# schematic.net
KiCad netlist of a schematic drawn in EasyEDA
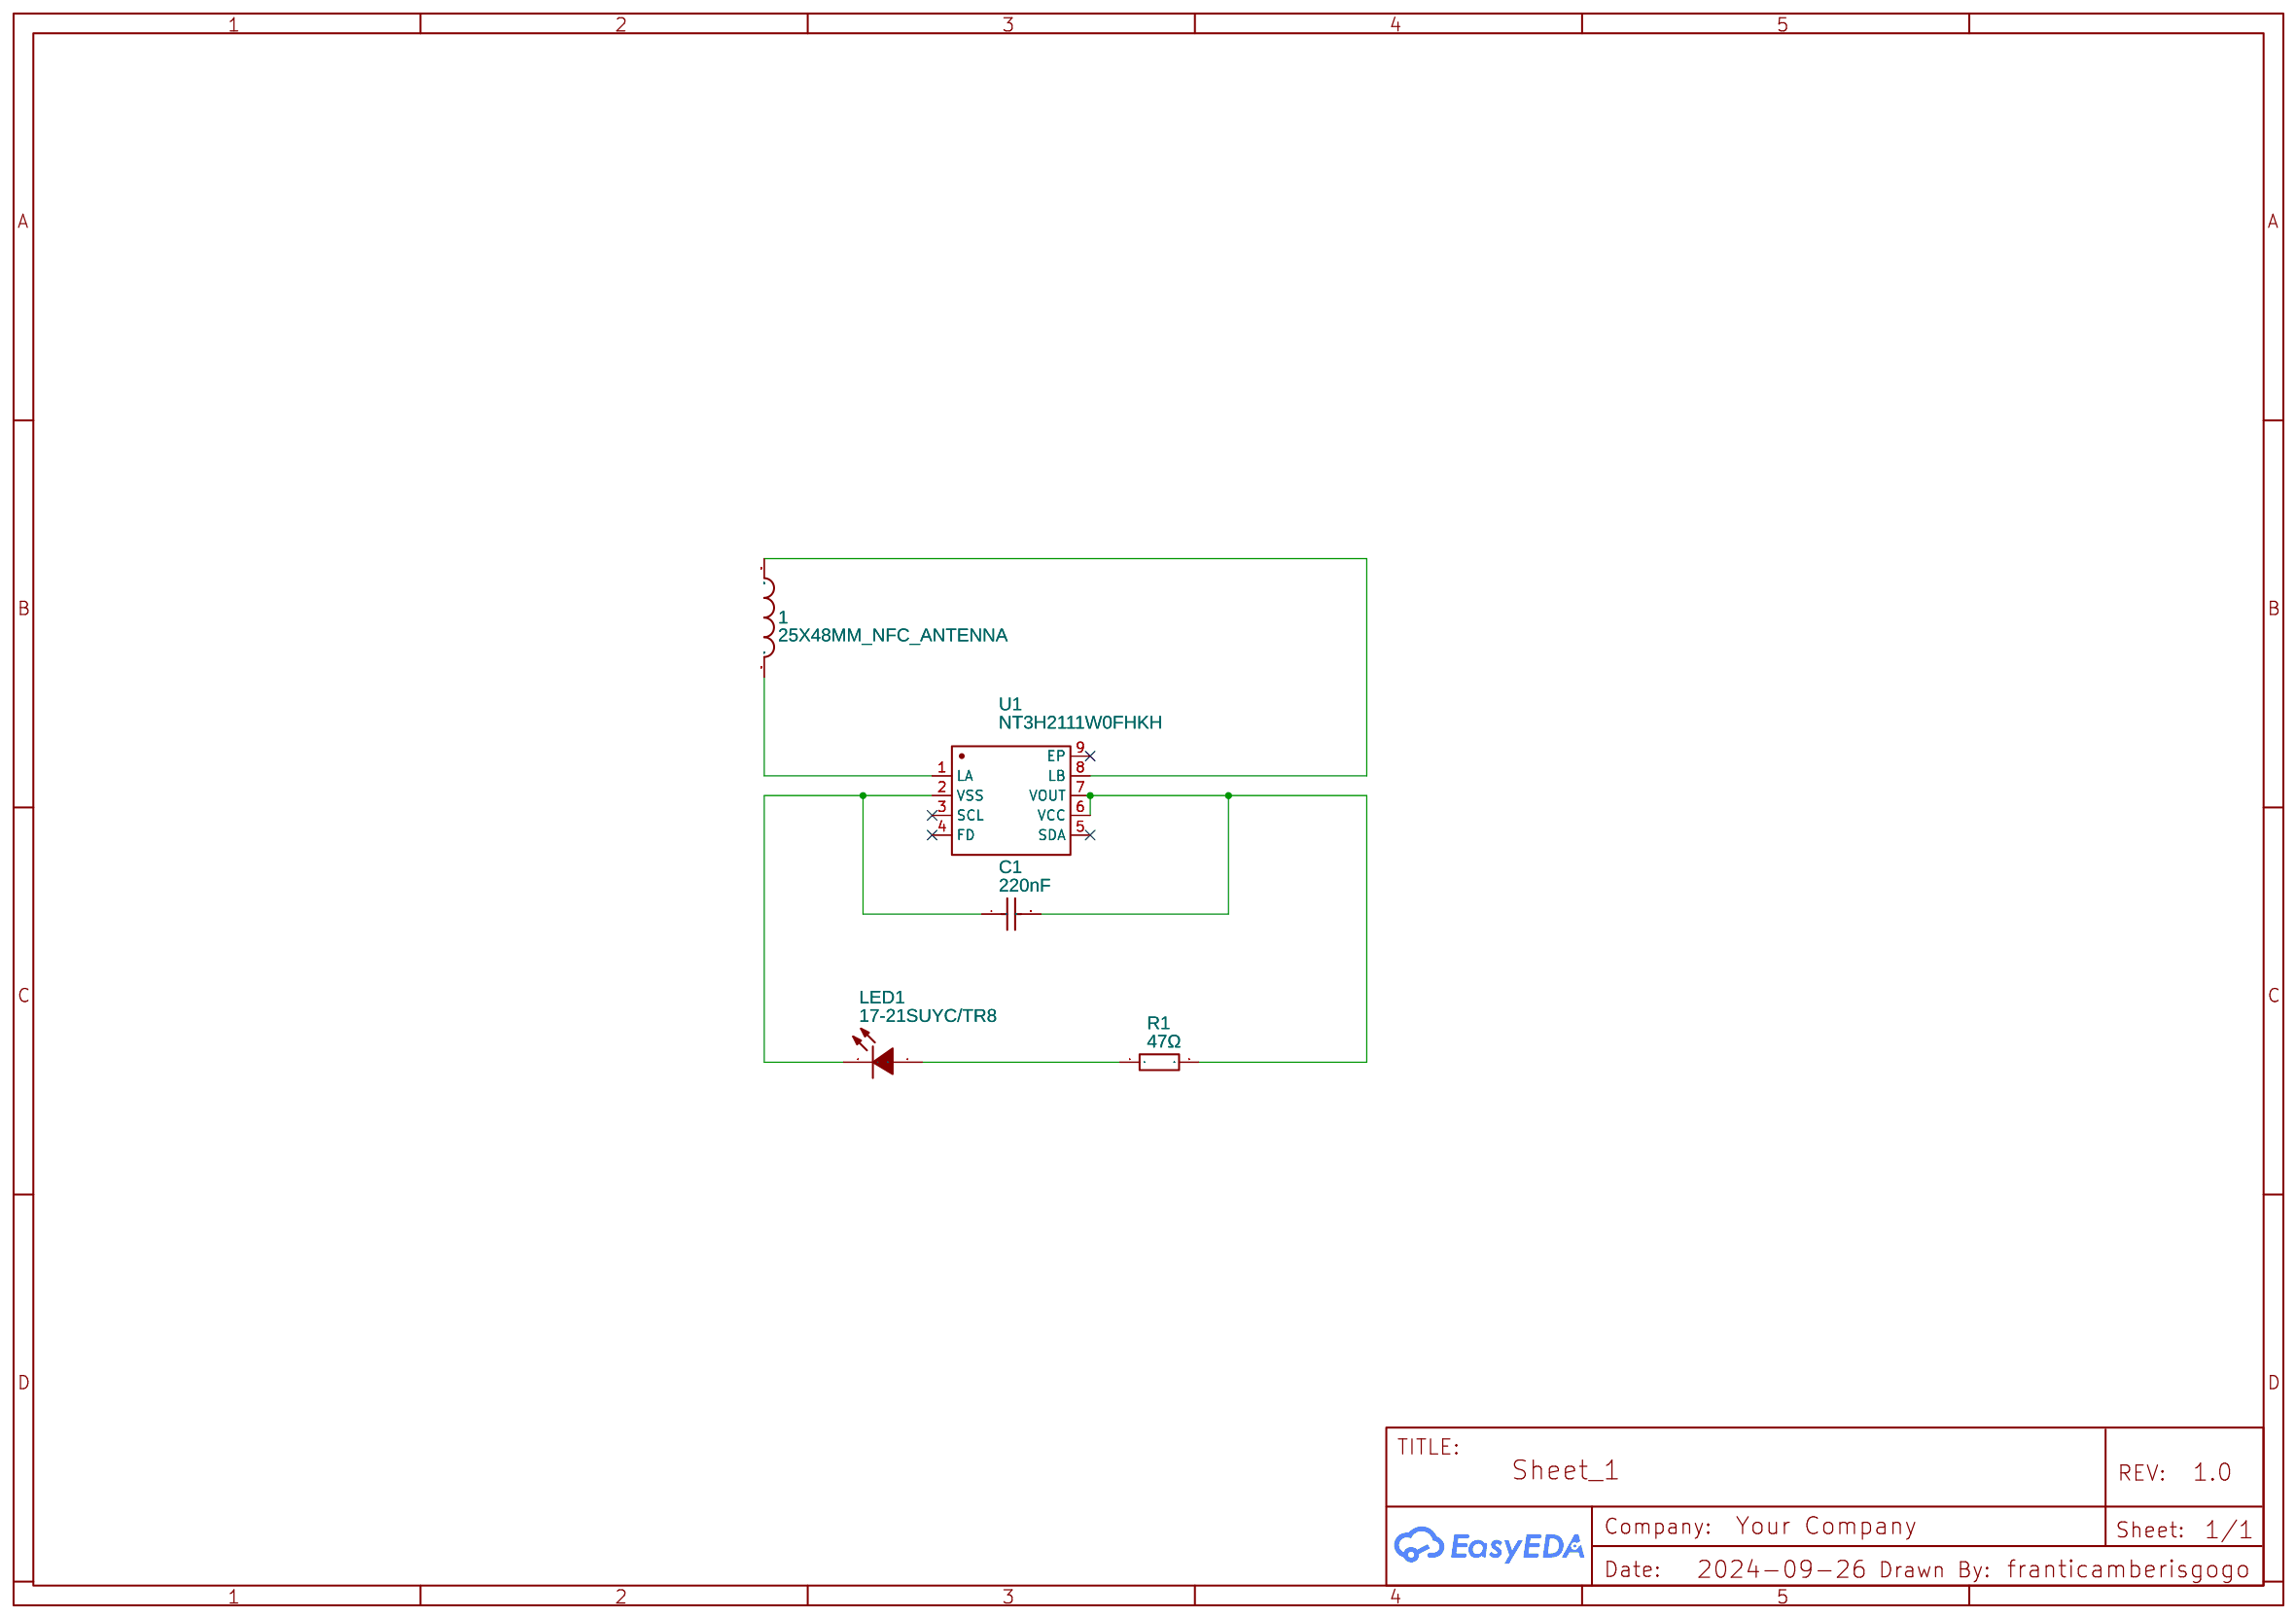
[diagram p0: schematic sheet]

(export (version "E")
  (design (tool "Eeschema 10.0.6"))
  (components
    (comp (ref "1") (value "25X48MM_NFC_ANTENNA") (libsource (lib "") (part "25X48MM_NFC_ANTENNA")))
    (comp (ref "C1")
      (value "220nF")
      (fields
        (field (name "Manufacturer Part") "CL10B224KA8NNNC")
        (field (name "Manufacturer") "SAMSUNG(三星)")
      )
      (libsource (lib "") (part "CL10B224KA8NNNC"))
    )
    (comp (ref "LED1")
      (value "17-21SUYC/TR8")
      (fields (field (name "Manufacturer Part") "KT-0805黄灯") (field (name "Manufacturer") "KENTO"))
      (libsource (lib "") (part "17-21SUYC/TR8"))
    )
    (comp (ref "R1")
      (value "47Ω")
      (fields
        (field (name "Manufacturer Part") "0603WAF470JT5E")
        (field (name "Manufacturer") "UNI-ROYAL(厚声)")
      )
      (libsource (lib "") (part "0603WAF470JT5E"))
    )
    (comp (ref "U1")
      (value "NT3H2111W0FHKH")
      (fields (field (name "Manufacturer") "NXP(恩智浦)"))
      (libsource (lib "") (part "NT3H2111W0FHKH"))
    )
  )
  (nets
    (net (code "1") (name "Net-(LED1-+)") (class "Default")
      (node (ref "LED1") (pin "1") (pinfunction "+_1") (pintype "unspecified"))
      (node (ref "R1") (pin "1") (pinfunction "1_1") (pintype "input"))
    )
    (net (code "2") (name "Net-(LED1--)") (class "Default")
      (node (ref "C1") (pin "1") (pinfunction "1_1") (pintype "input"))
      (node (ref "LED1") (pin "2") (pinfunction "-_2") (pintype "unspecified"))
      (node (ref "U1") (pin "2") (pinfunction "VSS_2") (pintype "unspecified"))
    )
    (net (code "3") (name "Net-(U1-LA)") (class "Default")
      (node (ref "1") (pin "P$2") (pinfunction "P$2_P$2") (pintype "bidirectional"))
      (node (ref "U1") (pin "1") (pinfunction "LA_1") (pintype "unspecified"))
    )
    (net (code "4") (name "Net-(U1-LB)") (class "Default")
      (node (ref "1") (pin "P$1") (pinfunction "P$1_P$1") (pintype "bidirectional"))
      (node (ref "U1") (pin "8") (pinfunction "LB_8") (pintype "unspecified"))
    )
    (net (code "5") (name "Net-(U1-VCC)") (class "Default")
      (node (ref "C1") (pin "2") (pinfunction "2_2") (pintype "input"))
      (node (ref "R1") (pin "2") (pinfunction "2_2") (pintype "input"))
      (node (ref "U1") (pin "6") (pinfunction "VCC_6") (pintype "unspecified"))
      (node (ref "U1") (pin "7") (pinfunction "VOUT_7") (pintype "unspecified"))
    )
    (net (code "6") (name "unconnected-(U1-EP-Pad9)") (class "Default")
      (node (ref "U1") (pin "9") (pinfunction "EP_9") (pintype "unspecified+no_connect"))
    )
    (net (code "7") (name "unconnected-(U1-FD-Pad4)") (class "Default")
      (node (ref "U1") (pin "4") (pinfunction "FD_4") (pintype "unspecified+no_connect"))
    )
    (net (code "8") (name "unconnected-(U1-SCL-Pad3)") (class "Default")
      (node (ref "U1") (pin "3") (pinfunction "SCL_3") (pintype "unspecified+no_connect"))
    )
    (net (code "9") (name "unconnected-(U1-SDA-Pad5)") (class "Default")
      (node (ref "U1") (pin "5") (pinfunction "SDA_5") (pintype "unspecified+no_connect"))
    )
  )
)
